# PCB_Hacker_Card_Share_Schematics_EasyEDA.net
KiCad netlist of a schematic drawn in EasyEDA
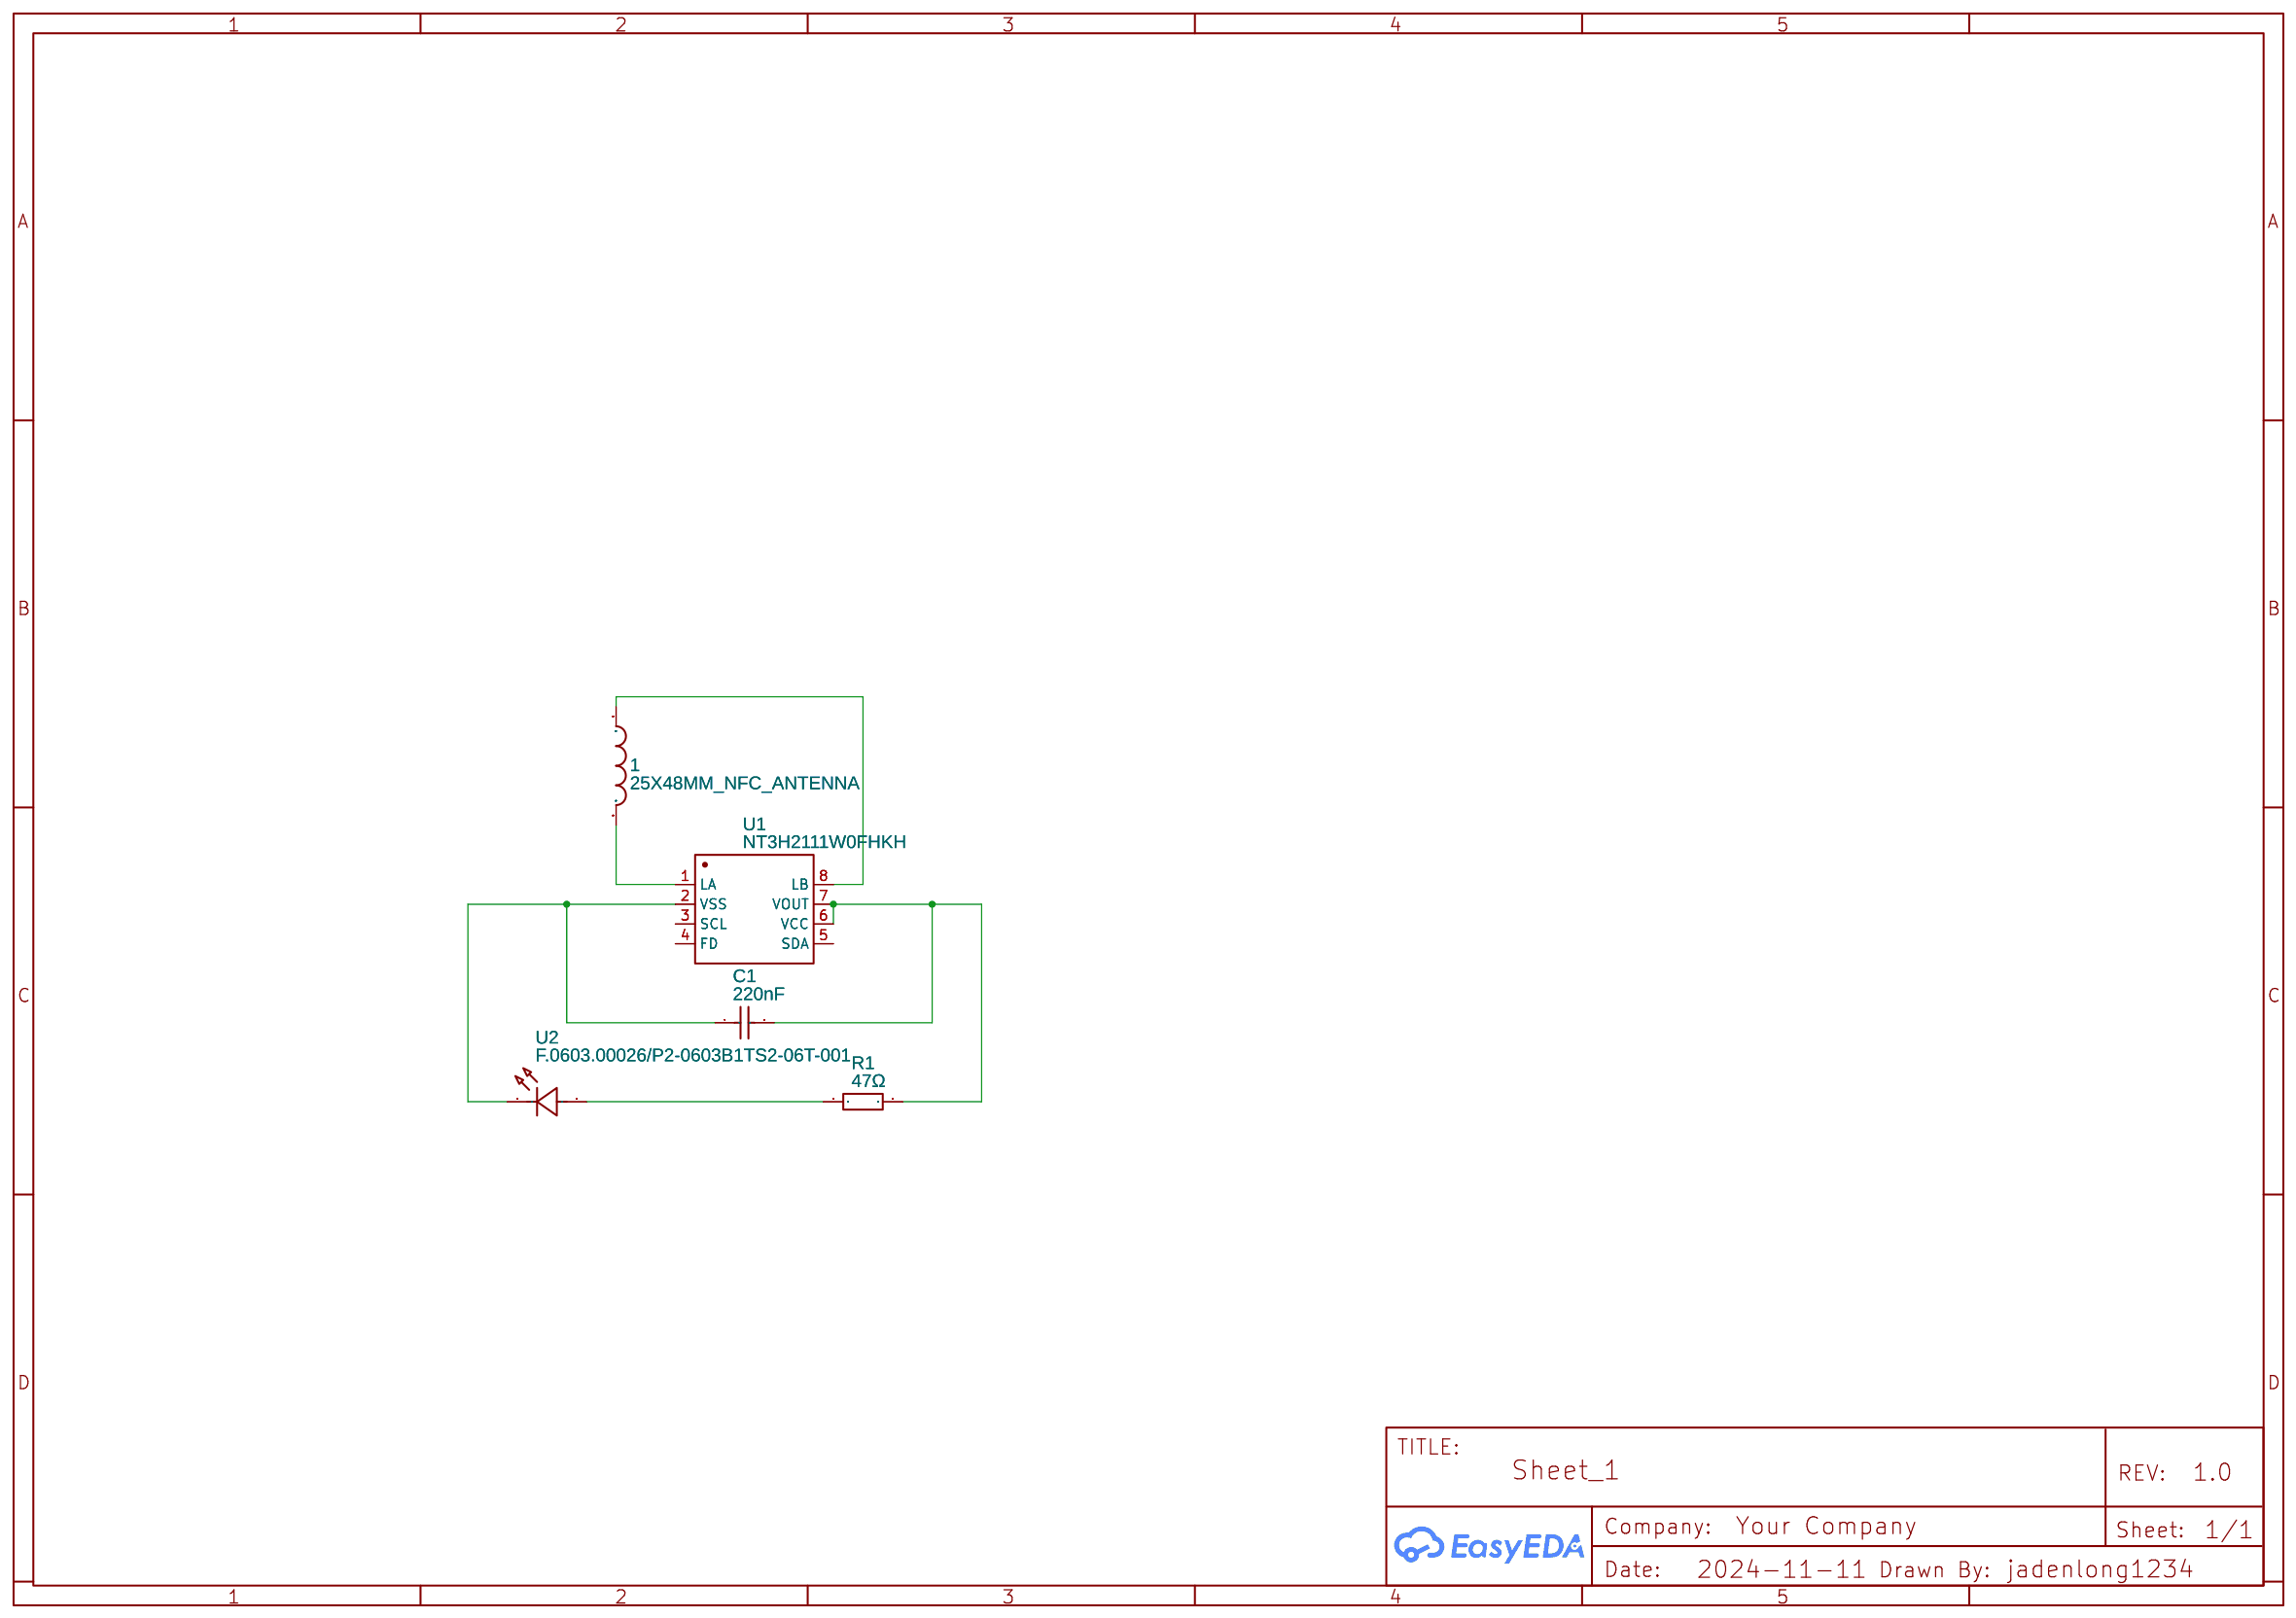
[diagram p0: schematic sheet]

(export (version "E")
  (design (tool "Eeschema 10.0.6"))
  (components
    (comp (ref "1") (value "25X48MM_NFC_ANTENNA") (libsource (lib "") (part "25X48MM_NFC_ANTENNA")))
    (comp (ref "C1")
      (value "220nF")
      (fields
        (field (name "Manufacturer Part") "CL10B224KA8NNNC")
        (field (name "Manufacturer") "SAMSUNG(三星)")
      )
      (libsource (lib "") (part "CL10B224KA8NNNC"))
    )
    (comp (ref "R1")
      (value "47Ω")
      (fields
        (field (name "Manufacturer Part") "0603WAF470JT5E")
        (field (name "Manufacturer") "UNI-ROYAL(厚声)")
      )
      (libsource (lib "") (part "0603WAF470JT5E"))
    )
    (comp (ref "U1")
      (value "NT3H2111W0FHKH")
      (fields (field (name "Manufacturer") "NXP(恩智浦)"))
      (libsource (lib "") (part "NT3H2111W0FHKH"))
    )
    (comp (ref "U2")
      (value "F.0603.00026/P2-0603B1TS2-06T-001")
      (fields (field (name "Manufacturer") "TUOZHAN(拓展光电)"))
      (libsource (lib "") (part "F.0603.00026/P2-0603B1TS2-06T-001"))
    )
  )
  (nets
    (net (code "1") (name "Net-(U1-LA)") (class "Default")
      (node (ref "1") (pin "P$2") (pinfunction "P$2_P$2") (pintype "bidirectional"))
      (node (ref "U1") (pin "1") (pinfunction "LA_1") (pintype "unspecified"))
    )
    (net (code "2") (name "Net-(U1-LB)") (class "Default")
      (node (ref "1") (pin "P$1") (pinfunction "P$1_P$1") (pintype "bidirectional"))
      (node (ref "U1") (pin "8") (pinfunction "LB_8") (pintype "unspecified"))
    )
    (net (code "3") (name "Net-(U1-VCC)") (class "Default")
      (node (ref "C1") (pin "2") (pinfunction "2_2") (pintype "input"))
      (node (ref "R1") (pin "2") (pinfunction "2_2") (pintype "input"))
      (node (ref "U1") (pin "6") (pinfunction "VCC_6") (pintype "unspecified"))
      (node (ref "U1") (pin "7") (pinfunction "VOUT_7") (pintype "unspecified"))
    )
    (net (code "4") (name "Net-(U1-VSS)") (class "Default")
      (node (ref "C1") (pin "1") (pinfunction "1_1") (pintype "input"))
      (node (ref "U1") (pin "2") (pinfunction "VSS_2") (pintype "unspecified"))
      (node (ref "U2") (pin "1") (pinfunction "K_1") (pintype "unspecified"))
    )
    (net (code "5") (name "Net-(U2-A)") (class "Default")
      (node (ref "R1") (pin "1") (pinfunction "1_1") (pintype "input"))
      (node (ref "U2") (pin "2") (pinfunction "A_2") (pintype "unspecified"))
    )
    (net (code "6") (name "unconnected-(U1-FD-Pad4)") (class "Default")
      (node (ref "U1") (pin "4") (pinfunction "FD_4") (pintype "unspecified"))
    )
    (net (code "7") (name "unconnected-(U1-SCL-Pad3)") (class "Default")
      (node (ref "U1") (pin "3") (pinfunction "SCL_3") (pintype "unspecified"))
    )
    (net (code "8") (name "unconnected-(U1-SDA-Pad5)") (class "Default")
      (node (ref "U1") (pin "5") (pinfunction "SDA_5") (pintype "unspecified"))
    )
  )
)
